# Sheet_5.net
KiCad netlist of a schematic drawn in Altium Designer
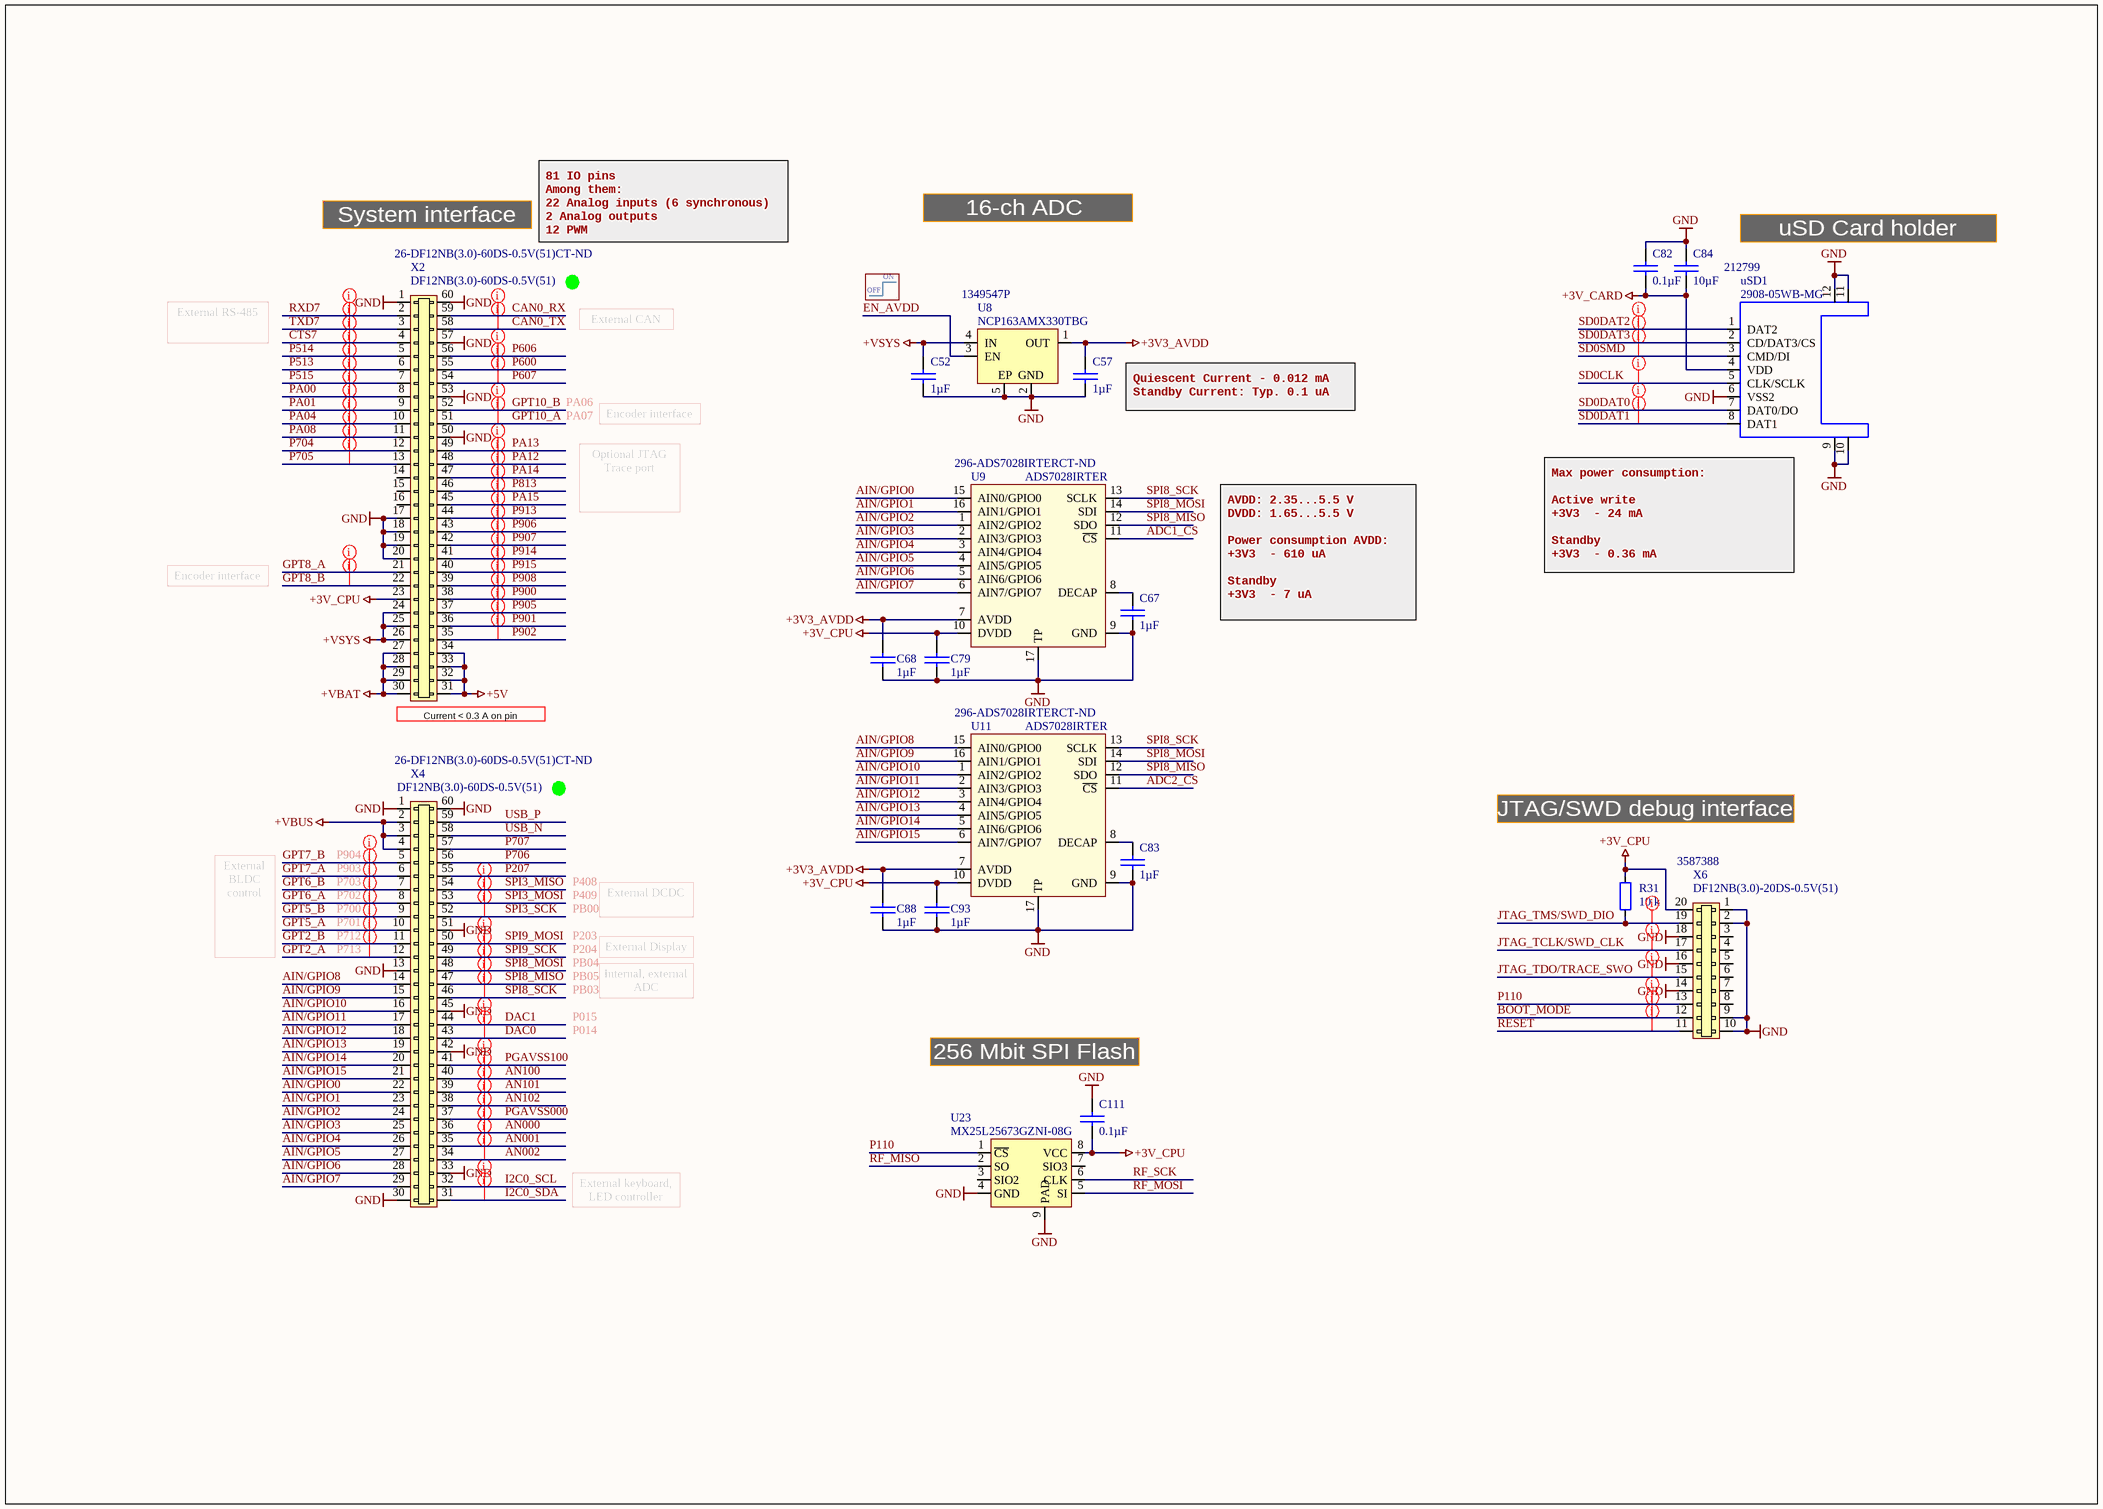
[diagram p0: Sheet_5.SchDoc]

(export (version "E")
  (design (tool "Eeschema 10.0.6"))
  (components
    (comp (ref "C52")
      (value "1µF")
      (footprint "0402 CAP")
      (description "1µF, ±20%, 25V, X5R, 0402 (1005 Metric), -55°C ~ 85°C, -, General Purpose")
      (fields (field (name "PART NUMBER") "TMK105BJ105MV-F") (field (name "MANUFACTURER") "Taiyo Yuden"))
      (libsource (lib "ea_PassivComps") (part "Capacitor"))
    )
    (comp (ref "C57")
      (value "1µF")
      (footprint "0402 CAP")
      (description "1µF, ±20%, 25V, X5R, 0402 (1005 Metric), -55°C ~ 85°C, -, General Purpose")
      (fields (field (name "PART NUMBER") "TMK105BJ105MV-F") (field (name "MANUFACTURER") "Taiyo Yuden"))
      (libsource (lib "ea_PassivComps") (part "Capacitor"))
    )
    (comp (ref "C67")
      (value "1µF")
      (footprint "0402 CAP")
      (description "1µF, ±20%, 25V, X5R, 0402 (1005 Metric), -55°C ~ 85°C, -, General Purpose")
      (fields (field (name "PART NUMBER") "TMK105BJ105MV-F") (field (name "MANUFACTURER") "Taiyo Yuden"))
      (libsource (lib "ea_PassivComps") (part "Capacitor"))
    )
    (comp (ref "C68")
      (value "1µF")
      (footprint "0402 CAP")
      (description "1µF, ±20%, 25V, X5R, 0402 (1005 Metric), -55°C ~ 85°C, -, General Purpose")
      (fields (field (name "PART NUMBER") "TMK105BJ105MV-F") (field (name "MANUFACTURER") "Taiyo Yuden"))
      (libsource (lib "ea_PassivComps") (part "Capacitor"))
    )
    (comp (ref "C79")
      (value "1µF")
      (footprint "0402 CAP")
      (description "1µF, ±20%, 25V, X5R, 0402 (1005 Metric), -55°C ~ 85°C, -, General Purpose")
      (fields (field (name "PART NUMBER") "TMK105BJ105MV-F") (field (name "MANUFACTURER") "Taiyo Yuden"))
      (libsource (lib "ea_PassivComps") (part "Capacitor"))
    )
    (comp (ref "C82")
      (value "0.1µF")
      (footprint "0402 CAP")
      (description "0.1µF, ±10%, 50V, X7R, 0402 (1005 Metric), -55°C ~ 125°C, -, General Purpose")
      (fields
        (field (name "PART NUMBER") "0402B104K500CT")
        (field (name "MANUFACTURER") "Walsin Technology Corporation")
      )
      (libsource (lib "ea_PassivComps") (part "Capacitor"))
    )
    (comp (ref "C83")
      (value "1µF")
      (footprint "0402 CAP")
      (description "1µF, ±20%, 25V, X5R, 0402 (1005 Metric), -55°C ~ 85°C, -, General Purpose")
      (fields (field (name "PART NUMBER") "TMK105BJ105MV-F") (field (name "MANUFACTURER") "Taiyo Yuden"))
      (libsource (lib "ea_PassivComps") (part "Capacitor"))
    )
    (comp (ref "C84")
      (value "10µF")
      (footprint "0603 CAP")
      (description "10µF, ±10%, 16V, X5R, 0603 (1608 Metric), -55°C ~ 85°C, -, Automotive")
      (fields
        (field (name "PART NUMBER") "GRT188R61C106KE13D")
        (field (name "MANUFACTURER") "Murata Electronics North America")
      )
      (libsource (lib "ea_PassivComps") (part "Capacitor"))
    )
    (comp (ref "C88")
      (value "1µF")
      (footprint "0402 CAP")
      (description "1µF, ±20%, 25V, X5R, 0402 (1005 Metric), -55°C ~ 85°C, -, General Purpose")
      (fields (field (name "PART NUMBER") "TMK105BJ105MV-F") (field (name "MANUFACTURER") "Taiyo Yuden"))
      (libsource (lib "ea_PassivComps") (part "Capacitor"))
    )
    (comp (ref "C93")
      (value "1µF")
      (footprint "0402 CAP")
      (description "1µF, ±20%, 25V, X5R, 0402 (1005 Metric), -55°C ~ 85°C, -, General Purpose")
      (fields (field (name "PART NUMBER") "TMK105BJ105MV-F") (field (name "MANUFACTURER") "Taiyo Yuden"))
      (libsource (lib "ea_PassivComps") (part "Capacitor"))
    )
    (comp (ref "C111")
      (value "0.1µF")
      (footprint "0402 CAP")
      (description "0.1µF, ±10%, 50V, X7R, 0402 (1005 Metric), -55°C ~ 125°C, -, General Purpose")
      (fields
        (field (name "PART NUMBER") "0402B104K500CT")
        (field (name "MANUFACTURER") "Walsin Technology Corporation")
      )
      (libsource (lib "ea_PassivComps") (part "Capacitor"))
    )
    (comp (ref "R31")
      (value "10 k")
      (footprint "0402")
      (fields
        (field (name "MANUFACTURER") "Stackpole Electronics Inc")
        (field (name "TOLERANCE") "±1%")
        (field (name "PARTNUM") "RMCF0402FT10K0CT-ND")
      )
      (libsource (lib "ea_PassivComps") (part "Resistor"))
    )
    (comp (ref "U8")
      (value "NCP163AMX330TBG")
      (footprint "4-XDFN")
      (description "LDO 3.3V, 250 mA, Vin < 5.5V, Iq < 20uA, -40..+125 C,  4-XDFN (1x1)")
      (fields
        (field (name "MANUFACTURER") "ON Semiconductor")
        (field (name "PARTNUM") "NCP163AMX330TBGOSCT-ND")
        (field (name "SUPPLIER PART NUMBER 1") "1349547P")
      )
      (libsource (lib "ea_IC_Linear_reg_LDO") (part "NCP163AMX330TBG"))
    )
    (comp (ref "U9")
      (value "ADS7028IRTER")
      (footprint "WQFN-16 3x3mm TI")
      (description "12 Bit Analog to Digital Converter 8 Input 1 SAR, 2.35V ~ 5.5V, 16-WQFN (3x3),  -40°C ~ 85°C")
      (fields
        (field (name "MANUFACTURER") "Texas Instruments")
        (field (name "PARTNUM") "296-ADS7028IRTERCT-ND")
        (field (name "SUPPLIER PART NUMBER 1") "296-ADS7028IRTERCT-ND")
      )
      (libsource (lib "ea_IC_ADC") (part "ADS7028IRTER"))
    )
    (comp (ref "U11")
      (value "ADS7028IRTER")
      (footprint "WQFN-16 3x3mm TI")
      (description "12 Bit Analog to Digital Converter 8 Input 1 SAR, 2.35V ~ 5.5V, 16-WQFN (3x3),  -40°C ~ 85°C")
      (fields
        (field (name "MANUFACTURER") "Texas Instruments")
        (field (name "PARTNUM") "296-ADS7028IRTERCT-ND")
        (field (name "SUPPLIER PART NUMBER 1") "296-ADS7028IRTERCT-ND")
      )
      (libsource (lib "ea_IC_ADC") (part "ADS7028IRTER"))
    )
    (comp (ref "U23")
      (value "MX25L25673GZNI-08G")
      (footprint "DFN8")
      (description "FLASH - NOR Memory IC 256Mbit SPI 120 MHz, 2.7V ~ 3.6V, 8-WSON (6x5), -40°C ~ 85°C (TA)")
      (fields
        (field (name "MANUFACTURER") "Kioxia America, Inc.")
        (field (name "PARTNUM") "TC58CVG1S3HRAIG-ND")
      )
      (libsource (lib "ea_IC_NOR_NAND_FLASH") (part "MX25L25673GZNI-08G"))
    )
    (comp (ref "uSD1")
      (value "2908-05WB-MG")
      (footprint "2908-05WB-MG")
      (description "microSD cadr holder")
      (fields (field (name "MANUFACTURER") "3M") (field (name "SUPPLIER PART NUMBER 1") "212799"))
      (libsource (lib "ea_CARD_holders") (part "2908-05WB-MG"))
    )
    (comp (ref "X2")
      (value "DF12NB(3.0)-60DS-0.5V(51)")
      (footprint "DF12NB(3.0)-60DS-0.5V(51)")
      (fields
        (field (name "MANUFACTURER") "Hirose Electric")
        (field (name "PARTNUM") "26-DF12NB(3.0)-60DS-0.5V(51)CT-ND")
        (field (name "SUPPLIER PART NUMBER 1") "26-DF12NB(3.0)-60DS-0.5V(51)CT-ND")
      )
      (libsource (lib "ea_Connectors_0.5_mm_pitch") (part "DF12NB(3.0)-60DS-0.5V(51)"))
    )
    (comp (ref "X4")
      (value "DF12NB(3.0)-60DS-0.5V(51)")
      (footprint "DF12NB(3.0)-60DS-0.5V(51)")
      (fields
        (field (name "MANUFACTURER") "Hirose Electric")
        (field (name "PARTNUM") "26-DF12NB(3.0)-60DS-0.5V(51)CT-ND")
        (field (name "SUPPLIER PART NUMBER 1") "26-DF12NB(3.0)-60DS-0.5V(51)CT-ND")
      )
      (libsource (lib "ea_Connectors_0.5_mm_pitch") (part "DF12NB(3.0)-60DS-0.5V(51)"))
    )
    (comp (ref "X6")
      (value "DF12NB(3.0)-20DS-0.5V(51)")
      (footprint "DF12NB(3.0)-20DS-0.5V(51)")
      (fields
        (field (name "MANUFACTURER") "Hirose Electric")
        (field (name "PARTNUM") "26-DF12NB(3.0)-20DS-0.5V(51)CT-ND - Cut Tape (CT)")
        (field (name "SUPPLIER PART NUMBER 1") "3587388")
      )
      (libsource (lib "ea_Connectors_0.5_mm_pitch") (part "DF12NB(3.0)-20DS-0.5V(51)"))
    )
  )
  (nets
    (net (code "1") (name "+3V3_AVDD") (class "Default")
      (node (ref "C57") (pin "1") (pinfunction "1_1") (pintype "passive"))
      (node (ref "C68") (pin "1") (pinfunction "1_1") (pintype "passive"))
      (node (ref "C88") (pin "1") (pinfunction "1_1") (pintype "passive"))
      (node (ref "U11") (pin "7") (pinfunction "AVDD_7") (pintype "passive"))
      (node (ref "U8") (pin "1") (pinfunction "OUT_1") (pintype "power_in"))
      (node (ref "U9") (pin "7") (pinfunction "AVDD_7") (pintype "passive"))
    )
    (net (code "2") (name "+3V_CARD") (class "Default")
      (node (ref "C82") (pin "2") (pinfunction "2_2") (pintype "passive"))
      (node (ref "C84") (pin "2") (pinfunction "2_2") (pintype "passive"))
      (node (ref "uSD1") (pin "4") (pinfunction "VDD_4") (pintype "passive"))
    )
    (net (code "3") (name "+3V_CPU") (class "Default")
      (node (ref "C111") (pin "2") (pinfunction "2_2") (pintype "passive"))
      (node (ref "C79") (pin "1") (pinfunction "1_1") (pintype "passive"))
      (node (ref "C93") (pin "1") (pinfunction "1_1") (pintype "passive"))
      (node (ref "R31") (pin "2") (pinfunction "2_2") (pintype "passive"))
      (node (ref "U11") (pin "10") (pinfunction "DVDD_10") (pintype "passive"))
      (node (ref "U23") (pin "8") (pinfunction "VCC_8") (pintype "passive"))
      (node (ref "U9") (pin "10") (pinfunction "DVDD_10") (pintype "passive"))
      (node (ref "X2") (pin "23") (pinfunction "23_23") (pintype "passive"))
      (node (ref "X6") (pin "20") (pinfunction "11_20") (pintype "passive"))
    )
    (net (code "4") (name "+5V") (class "Default")
      (node (ref "X2") (pin "31") (pinfunction "31_31") (pintype "passive"))
      (node (ref "X2") (pin "32") (pinfunction "32_32") (pintype "passive"))
      (node (ref "X2") (pin "33") (pinfunction "33_33") (pintype "passive"))
      (node (ref "X2") (pin "34") (pinfunction "34_34") (pintype "passive"))
    )
    (net (code "5") (name "+VBAT") (class "Default")
      (node (ref "X2") (pin "27") (pinfunction "27_27") (pintype "passive"))
      (node (ref "X2") (pin "28") (pinfunction "28_28") (pintype "passive"))
      (node (ref "X2") (pin "29") (pinfunction "29_29") (pintype "passive"))
      (node (ref "X2") (pin "30") (pinfunction "30_30") (pintype "passive"))
    )
    (net (code "6") (name "+VBUS") (class "Default")
      (node (ref "X4") (pin "2") (pinfunction "2_2") (pintype "passive"))
      (node (ref "X4") (pin "3") (pinfunction "3_3") (pintype "passive"))
      (node (ref "X4") (pin "4") (pinfunction "4_4") (pintype "passive"))
    )
    (net (code "7") (name "+VSYS") (class "Default")
      (node (ref "C52") (pin "1") (pinfunction "1_1") (pintype "passive"))
      (node (ref "U8") (pin "4") (pinfunction "IN_4") (pintype "power_in"))
      (node (ref "X2") (pin "24") (pinfunction "24_24") (pintype "passive"))
      (node (ref "X2") (pin "25") (pinfunction "25_25") (pintype "passive"))
      (node (ref "X2") (pin "26") (pinfunction "26_26") (pintype "passive"))
    )
    (net (code "8") (name "/ADC1_CS") (class "Default")
      (node (ref "U9") (pin "11") (pinfunction "~{CS}_11") (pintype "passive"))
    )
    (net (code "9") (name "/ADC2_CS") (class "Default")
      (node (ref "U11") (pin "11") (pinfunction "~{CS}_11") (pintype "passive"))
    )
    (net (code "10") (name "/AIN{slash}GPIO0") (class "Default")
      (node (ref "U9") (pin "15") (pinfunction "AIN0/GPIO0_15") (pintype "passive"))
      (node (ref "X4") (pin "22") (pinfunction "22_22") (pintype "passive"))
    )
    (net (code "11") (name "/AIN{slash}GPIO1") (class "Default")
      (node (ref "U9") (pin "16") (pinfunction "AIN1/GPIO1_16") (pintype "passive"))
      (node (ref "X4") (pin "23") (pinfunction "23_23") (pintype "passive"))
    )
    (net (code "12") (name "/AIN{slash}GPIO2") (class "Default")
      (node (ref "U9") (pin "1") (pinfunction "AIN2/GPIO2_1") (pintype "passive"))
      (node (ref "X4") (pin "24") (pinfunction "24_24") (pintype "passive"))
    )
    (net (code "13") (name "/AIN{slash}GPIO3") (class "Default")
      (node (ref "U9") (pin "2") (pinfunction "AIN3/GPIO3_2") (pintype "passive"))
      (node (ref "X4") (pin "25") (pinfunction "25_25") (pintype "passive"))
    )
    (net (code "14") (name "/AIN{slash}GPIO4") (class "Default")
      (node (ref "U9") (pin "3") (pinfunction "AIN4/GPIO4_3") (pintype "passive"))
      (node (ref "X4") (pin "26") (pinfunction "26_26") (pintype "passive"))
    )
    (net (code "15") (name "/AIN{slash}GPIO5") (class "Default")
      (node (ref "U9") (pin "4") (pinfunction "AIN5/GPIO5_4") (pintype "passive"))
      (node (ref "X4") (pin "27") (pinfunction "27_27") (pintype "passive"))
    )
    (net (code "16") (name "/AIN{slash}GPIO6") (class "Default")
      (node (ref "U9") (pin "5") (pinfunction "AIN6/GPIO6_5") (pintype "passive"))
      (node (ref "X4") (pin "28") (pinfunction "28_28") (pintype "passive"))
    )
    (net (code "17") (name "/AIN{slash}GPIO7") (class "Default")
      (node (ref "U9") (pin "6") (pinfunction "AIN7/GPIO7_6") (pintype "passive"))
      (node (ref "X4") (pin "29") (pinfunction "29_29") (pintype "passive"))
    )
    (net (code "18") (name "/AIN{slash}GPIO8") (class "Default")
      (node (ref "U11") (pin "15") (pinfunction "AIN0/GPIO0_15") (pintype "passive"))
      (node (ref "X4") (pin "14") (pinfunction "14_14") (pintype "passive"))
    )
    (net (code "19") (name "/AIN{slash}GPIO9") (class "Default")
      (node (ref "U11") (pin "16") (pinfunction "AIN1/GPIO1_16") (pintype "passive"))
      (node (ref "X4") (pin "15") (pinfunction "15_15") (pintype "passive"))
    )
    (net (code "20") (name "/AIN{slash}GPIO10") (class "Default")
      (node (ref "U11") (pin "1") (pinfunction "AIN2/GPIO2_1") (pintype "passive"))
      (node (ref "X4") (pin "16") (pinfunction "16_16") (pintype "passive"))
    )
    (net (code "21") (name "/AIN{slash}GPIO11") (class "Default")
      (node (ref "U11") (pin "2") (pinfunction "AIN3/GPIO3_2") (pintype "passive"))
      (node (ref "X4") (pin "17") (pinfunction "17_17") (pintype "passive"))
    )
    (net (code "22") (name "/AIN{slash}GPIO12") (class "Default")
      (node (ref "U11") (pin "3") (pinfunction "AIN4/GPIO4_3") (pintype "passive"))
      (node (ref "X4") (pin "18") (pinfunction "18_18") (pintype "passive"))
    )
    (net (code "23") (name "/AIN{slash}GPIO13") (class "Default")
      (node (ref "U11") (pin "4") (pinfunction "AIN5/GPIO5_4") (pintype "passive"))
      (node (ref "X4") (pin "19") (pinfunction "19_19") (pintype "passive"))
    )
    (net (code "24") (name "/AIN{slash}GPIO14") (class "Default")
      (node (ref "U11") (pin "5") (pinfunction "AIN6/GPIO6_5") (pintype "passive"))
      (node (ref "X4") (pin "20") (pinfunction "20_20") (pintype "passive"))
    )
    (net (code "25") (name "/AIN{slash}GPIO15") (class "Default")
      (node (ref "U11") (pin "6") (pinfunction "AIN7/GPIO7_6") (pintype "passive"))
      (node (ref "X4") (pin "21") (pinfunction "21_21") (pintype "passive"))
    )
    (net (code "26") (name "/AN000") (class "Default")
      (node (ref "X4") (pin "36") (pinfunction "36_36") (pintype "passive"))
    )
    (net (code "27") (name "/AN001") (class "Default")
      (node (ref "X4") (pin "35") (pinfunction "35_35") (pintype "passive"))
    )
    (net (code "28") (name "/AN002") (class "Default")
      (node (ref "X4") (pin "34") (pinfunction "34_34") (pintype "passive"))
    )
    (net (code "29") (name "/AN100") (class "Default")
      (node (ref "X4") (pin "40") (pinfunction "40_40") (pintype "passive"))
    )
    (net (code "30") (name "/AN101") (class "Default")
      (node (ref "X4") (pin "39") (pinfunction "39_39") (pintype "passive"))
    )
    (net (code "31") (name "/AN102") (class "Default")
      (node (ref "X4") (pin "38") (pinfunction "38_38") (pintype "passive"))
    )
    (net (code "32") (name "/BOOT_MODE") (class "Default")
      (node (ref "X6") (pin "12") (pinfunction "7_12") (pintype "passive"))
    )
    (net (code "33") (name "/CAN0_RX") (class "Default")
      (node (ref "X2") (pin "59") (pinfunction "59_59") (pintype "passive"))
    )
    (net (code "34") (name "/CAN0_TX") (class "Default")
      (node (ref "X2") (pin "58") (pinfunction "58_58") (pintype "passive"))
    )
    (net (code "35") (name "/CTS7") (class "Default")
      (node (ref "X2") (pin "4") (pinfunction "4_4") (pintype "passive"))
    )
    (net (code "36") (name "/DAC0") (class "Default")
      (node (ref "X4") (pin "43") (pinfunction "43_43") (pintype "passive"))
    )
    (net (code "37") (name "/DAC1") (class "Default")
      (node (ref "X4") (pin "44") (pinfunction "44_44") (pintype "passive"))
    )
    (net (code "38") (name "/EN_AVDD") (class "Default")
      (node (ref "U8") (pin "3") (pinfunction "EN_3") (pintype "power_in"))
    )
    (net (code "39") (name "/GPT2_A") (class "Default")
      (node (ref "X4") (pin "12") (pinfunction "12_12") (pintype "passive"))
    )
    (net (code "40") (name "/GPT2_B") (class "Default")
      (node (ref "X4") (pin "11") (pinfunction "11_11") (pintype "passive"))
    )
    (net (code "41") (name "/GPT5_A") (class "Default")
      (node (ref "X4") (pin "10") (pinfunction "10_10") (pintype "passive"))
    )
    (net (code "42") (name "/GPT5_B") (class "Default")
      (node (ref "X4") (pin "9") (pinfunction "9_9") (pintype "passive"))
    )
    (net (code "43") (name "/GPT6_A") (class "Default")
      (node (ref "X4") (pin "8") (pinfunction "8_8") (pintype "passive"))
    )
    (net (code "44") (name "/GPT6_B") (class "Default")
      (node (ref "X4") (pin "7") (pinfunction "7_7") (pintype "passive"))
    )
    (net (code "45") (name "/GPT7_A") (class "Default")
      (node (ref "X4") (pin "6") (pinfunction "6_6") (pintype "passive"))
    )
    (net (code "46") (name "/GPT7_B") (class "Default")
      (node (ref "X4") (pin "5") (pinfunction "5_5") (pintype "passive"))
    )
    (net (code "47") (name "/GPT8_A") (class "Default")
      (node (ref "X2") (pin "21") (pinfunction "21_21") (pintype "passive"))
    )
    (net (code "48") (name "/GPT8_B") (class "Default")
      (node (ref "X2") (pin "22") (pinfunction "22_22") (pintype "passive"))
    )
    (net (code "49") (name "/GPT10_A") (class "Default")
      (node (ref "X2") (pin "51") (pinfunction "51_51") (pintype "passive"))
    )
    (net (code "50") (name "/GPT10_B") (class "Default")
      (node (ref "X2") (pin "52") (pinfunction "52_52") (pintype "passive"))
    )
    (net (code "51") (name "/I2C0_SCL") (class "Default")
      (node (ref "X4") (pin "32") (pinfunction "32_32") (pintype "passive"))
    )
    (net (code "52") (name "/I2C0_SDA") (class "Default")
      (node (ref "X4") (pin "31") (pinfunction "31_31") (pintype "passive"))
    )
    (net (code "53") (name "/JTAG_TCLK{slash}SWD_CLK") (class "Default")
      (node (ref "X6") (pin "17") (pinfunction "9_17") (pintype "passive"))
    )
    (net (code "54") (name "/JTAG_TDO{slash}TRACE_SWO") (class "Default")
      (node (ref "X6") (pin "15") (pinfunction "8_15") (pintype "passive"))
    )
    (net (code "55") (name "/JTAG_TMS{slash}SWD_DIO") (class "Default")
      (node (ref "R31") (pin "1") (pinfunction "1_1") (pintype "passive"))
      (node (ref "X6") (pin "19") (pinfunction "10_19") (pintype "passive"))
    )
    (net (code "56") (name "/P110") (class "Default")
      (node (ref "U23") (pin "1") (pinfunction "~{CS}_1") (pintype "passive"))
      (node (ref "X6") (pin "13") (pinfunction "7_13") (pintype "passive"))
    )
    (net (code "57") (name "/P207") (class "Default")
      (node (ref "X4") (pin "55") (pinfunction "55_55") (pintype "passive"))
    )
    (net (code "58") (name "/P513") (class "Default")
      (node (ref "X2") (pin "6") (pinfunction "6_6") (pintype "passive"))
    )
    (net (code "59") (name "/P514") (class "Default")
      (node (ref "X2") (pin "5") (pinfunction "5_5") (pintype "passive"))
    )
    (net (code "60") (name "/P515") (class "Default")
      (node (ref "X2") (pin "7") (pinfunction "7_7") (pintype "passive"))
    )
    (net (code "61") (name "/P600") (class "Default")
      (node (ref "X2") (pin "55") (pinfunction "55_55") (pintype "passive"))
    )
    (net (code "62") (name "/P606") (class "Default")
      (node (ref "X2") (pin "56") (pinfunction "56_56") (pintype "passive"))
    )
    (net (code "63") (name "/P607") (class "Default")
      (node (ref "X2") (pin "54") (pinfunction "54_54") (pintype "passive"))
    )
    (net (code "64") (name "/P704") (class "Default")
      (node (ref "X2") (pin "12") (pinfunction "12_12") (pintype "passive"))
    )
    (net (code "65") (name "/P705") (class "Default")
      (node (ref "X2") (pin "13") (pinfunction "13_13") (pintype "passive"))
    )
    (net (code "66") (name "/P706") (class "Default")
      (node (ref "X4") (pin "56") (pinfunction "56_56") (pintype "passive"))
    )
    (net (code "67") (name "/P707") (class "Default")
      (node (ref "X4") (pin "57") (pinfunction "57_57") (pintype "passive"))
    )
    (net (code "68") (name "/P813") (class "Default")
      (node (ref "X2") (pin "46") (pinfunction "46_46") (pintype "passive"))
    )
    (net (code "69") (name "/P900") (class "Default")
      (node (ref "X2") (pin "38") (pinfunction "38_38") (pintype "passive"))
    )
    (net (code "70") (name "/P901") (class "Default")
      (node (ref "X2") (pin "36") (pinfunction "36_36") (pintype "passive"))
    )
    (net (code "71") (name "/P902") (class "Default")
      (node (ref "X2") (pin "35") (pinfunction "35_35") (pintype "passive"))
    )
    (net (code "72") (name "/P905") (class "Default")
      (node (ref "X2") (pin "37") (pinfunction "37_37") (pintype "passive"))
    )
    (net (code "73") (name "/P906") (class "Default")
      (node (ref "X2") (pin "43") (pinfunction "43_43") (pintype "passive"))
    )
    (net (code "74") (name "/P907") (class "Default")
      (node (ref "X2") (pin "42") (pinfunction "42_42") (pintype "passive"))
    )
    (net (code "75") (name "/P908") (class "Default")
      (node (ref "X2") (pin "39") (pinfunction "39_39") (pintype "passive"))
    )
    (net (code "76") (name "/P913") (class "Default")
      (node (ref "X2") (pin "44") (pinfunction "44_44") (pintype "passive"))
    )
    (net (code "77") (name "/P914") (class "Default")
      (node (ref "X2") (pin "41") (pinfunction "41_41") (pintype "passive"))
    )
    (net (code "78") (name "/P915") (class "Default")
      (node (ref "X2") (pin "40") (pinfunction "40_40") (pintype "passive"))
    )
    (net (code "79") (name "/PA00") (class "Default")
      (node (ref "X2") (pin "8") (pinfunction "8_8") (pintype "passive"))
    )
    (net (code "80") (name "/PA01") (class "Default")
      (node (ref "X2") (pin "9") (pinfunction "9_9") (pintype "passive"))
    )
    (net (code "81") (name "/PA04") (class "Default")
      (node (ref "X2") (pin "10") (pinfunction "10_10") (pintype "passive"))
    )
    (net (code "82") (name "/PA08") (class "Default")
      (node (ref "X2") (pin "11") (pinfunction "11_11") (pintype "passive"))
    )
    (net (code "83") (name "/PA12") (class "Default")
      (node (ref "X2") (pin "48") (pinfunction "48_48") (pintype "passive"))
    )
    (net (code "84") (name "/PA13") (class "Default")
      (node (ref "X2") (pin "49") (pinfunction "49_49") (pintype "passive"))
    )
    (net (code "85") (name "/PA14") (class "Default")
      (node (ref "X2") (pin "47") (pinfunction "47_47") (pintype "passive"))
    )
    (net (code "86") (name "/PA15") (class "Default")
      (node (ref "X2") (pin "45") (pinfunction "45_45") (pintype "passive"))
    )
    (net (code "87") (name "/PGAVSS000") (class "Default")
      (node (ref "X4") (pin "37") (pinfunction "37_37") (pintype "passive"))
    )
    (net (code "88") (name "/PGAVSS100") (class "Default")
      (node (ref "X4") (pin "41") (pinfunction "41_41") (pintype "passive"))
    )
    (net (code "89") (name "/RESET") (class "Default")
      (node (ref "X6") (pin "11") (pinfunction "6_11") (pintype "passive"))
    )
    (net (code "90") (name "/RF_MISO") (class "Default")
      (node (ref "U23") (pin "2") (pinfunction "SO_2") (pintype "passive"))
    )
    (net (code "91") (name "/RF_MOSI") (class "Default")
      (node (ref "U23") (pin "5") (pinfunction "SI_5") (pintype "passive"))
    )
    (net (code "92") (name "/RF_SCK") (class "Default")
      (node (ref "U23") (pin "6") (pinfunction "CLK_6") (pintype "passive"))
    )
    (net (code "93") (name "/RXD7") (class "Default")
      (node (ref "X2") (pin "2") (pinfunction "2_2") (pintype "passive"))
    )
    (net (code "94") (name "/SD0CLK") (class "Default")
      (node (ref "uSD1") (pin "5") (pinfunction "CLK/SCLK_5") (pintype "passive"))
    )
    (net (code "95") (name "/SD0DAT0") (class "Default")
      (node (ref "uSD1") (pin "7") (pinfunction "DAT0/DO_7") (pintype "passive"))
    )
    (net (code "96") (name "/SD0DAT1") (class "Default")
      (node (ref "uSD1") (pin "8") (pinfunction "DAT1_8") (pintype "passive"))
    )
    (net (code "97") (name "/SD0DAT2") (class "Default")
      (node (ref "uSD1") (pin "1") (pinfunction "DAT2_1") (pintype "passive"))
    )
    (net (code "98") (name "/SD0DAT3") (class "Default")
      (node (ref "uSD1") (pin "2") (pinfunction "CD/DAT3/CS_2") (pintype "passive"))
    )
    (net (code "99") (name "/SD0SMD") (class "Default")
      (node (ref "uSD1") (pin "3") (pinfunction "CMD/DI_3") (pintype "passive"))
    )
    (net (code "100") (name "/SPI3_MISO") (class "Default")
      (node (ref "X4") (pin "54") (pinfunction "54_54") (pintype "passive"))
    )
    (net (code "101") (name "/SPI3_MOSI") (class "Default")
      (node (ref "X4") (pin "53") (pinfunction "53_53") (pintype "passive"))
    )
    (net (code "102") (name "/SPI3_SCK") (class "Default")
      (node (ref "X4") (pin "52") (pinfunction "52_52") (pintype "passive"))
    )
    (net (code "103") (name "/SPI8_MISO") (class "Default")
      (node (ref "U11") (pin "12") (pinfunction "SDO_12") (pintype "passive"))
      (node (ref "U9") (pin "12") (pinfunction "SDO_12") (pintype "passive"))
      (node (ref "X4") (pin "47") (pinfunction "47_47") (pintype "passive"))
    )
    (net (code "104") (name "/SPI8_MOSI") (class "Default")
      (node (ref "U11") (pin "14") (pinfunction "SDI_14") (pintype "passive"))
      (node (ref "U9") (pin "14") (pinfunction "SDI_14") (pintype "passive"))
      (node (ref "X4") (pin "48") (pinfunction "48_48") (pintype "passive"))
    )
    (net (code "105") (name "/SPI8_SCK") (class "Default")
      (node (ref "U11") (pin "13") (pinfunction "SCLK_13") (pintype "passive"))
      (node (ref "U9") (pin "13") (pinfunction "SCLK_13") (pintype "passive"))
      (node (ref "X4") (pin "46") (pinfunction "46_46") (pintype "passive"))
    )
    (net (code "106") (name "/SPI9_MOSI") (class "Default")
      (node (ref "X4") (pin "50") (pinfunction "50_50") (pintype "passive"))
    )
    (net (code "107") (name "/SPI9_SCK") (class "Default")
      (node (ref "X4") (pin "49") (pinfunction "49_49") (pintype "passive"))
    )
    (net (code "108") (name "/TXD7") (class "Default")
      (node (ref "X2") (pin "3") (pinfunction "3_3") (pintype "passive"))
    )
    (net (code "109") (name "/USB_N") (class "Default")
      (node (ref "X4") (pin "58") (pinfunction "58_58") (pintype "passive"))
    )
    (net (code "110") (name "/USB_P") (class "Default")
      (node (ref "X4") (pin "59") (pinfunction "59_59") (pintype "passive"))
    )
    (net (code "111") (name "GND") (class "Default")
      (node (ref "C111") (pin "1") (pinfunction "1_1") (pintype "passive"))
      (node (ref "C52") (pin "2") (pinfunction "2_2") (pintype "passive"))
      (node (ref "C57") (pin "2") (pinfunction "2_2") (pintype "passive"))
      (node (ref "C67") (pin "2") (pinfunction "2_2") (pintype "passive"))
      (node (ref "C68") (pin "2") (pinfunction "2_2") (pintype "passive"))
      (node (ref "C79") (pin "2") (pinfunction "2_2") (pintype "passive"))
      (node (ref "C82") (pin "1") (pinfunction "1_1") (pintype "passive"))
      (node (ref "C83") (pin "2") (pinfunction "2_2") (pintype "passive"))
      (node (ref "C84") (pin "1") (pinfunction "1_1") (pintype "passive"))
      (node (ref "C88") (pin "2") (pinfunction "2_2") (pintype "passive"))
      (node (ref "C93") (pin "2") (pinfunction "2_2") (pintype "passive"))
      (node (ref "U11") (pin "17") (pinfunction "TP_17") (pintype "passive"))
      (node (ref "U11") (pin "9") (pinfunction "GND_9") (pintype "passive"))
      (node (ref "U23") (pin "4") (pinfunction "GND_4") (pintype "passive"))
      (node (ref "U23") (pin "9") (pinfunction "PAD_9") (pintype "passive"))
      (node (ref "U8") (pin "2") (pinfunction "GND_2") (pintype "power_in"))
      (node (ref "U8") (pin "5") (pinfunction "EP_5") (pintype "power_in"))
      (node (ref "U9") (pin "17") (pinfunction "TP_17") (pintype "passive"))
      (node (ref "U9") (pin "9") (pinfunction "GND_9") (pintype "passive"))
      (node (ref "X2") (pin "1") (pinfunction "1_1") (pintype "passive"))
      (node (ref "X2") (pin "17") (pinfunction "17_17") (pintype "passive"))
      (node (ref "X2") (pin "18") (pinfunction "18_18") (pintype "passive"))
      (node (ref "X2") (pin "19") (pinfunction "19_19") (pintype "passive"))
      (node (ref "X2") (pin "20") (pinfunction "20_20") (pintype "passive"))
      (node (ref "X2") (pin "50") (pinfunction "50_50") (pintype "passive"))
      (node (ref "X2") (pin "53") (pinfunction "53_53") (pintype "passive"))
      (node (ref "X2") (pin "57") (pinfunction "57_57") (pintype "passive"))
      (node (ref "X2") (pin "60") (pinfunction "60_60") (pintype "passive"))
      (node (ref "X4") (pin "1") (pinfunction "1_1") (pintype "passive"))
      (node (ref "X4") (pin "13") (pinfunction "13_13") (pintype "passive"))
      (node (ref "X4") (pin "30") (pinfunction "30_30") (pintype "passive"))
      (node (ref "X4") (pin "33") (pinfunction "33_33") (pintype "passive"))
      (node (ref "X4") (pin "42") (pinfunction "42_42") (pintype "passive"))
      (node (ref "X4") (pin "45") (pinfunction "45_45") (pintype "passive"))
      (node (ref "X4") (pin "51") (pinfunction "51_51") (pintype "passive"))
      (node (ref "X4") (pin "60") (pinfunction "60_60") (pintype "passive"))
      (node (ref "X6") (pin "1") (pinfunction "1_1") (pintype "passive"))
      (node (ref "X6") (pin "10") (pinfunction "6_10") (pintype "passive"))
      (node (ref "X6") (pin "14") (pinfunction "8_14") (pintype "passive"))
      (node (ref "X6") (pin "16") (pinfunction "9_16") (pintype "passive"))
      (node (ref "X6") (pin "18") (pinfunction "10_18") (pintype "passive"))
      (node (ref "X6") (pin "2") (pinfunction "2_2") (pintype "passive"))
      (node (ref "X6") (pin "9") (pinfunction "5_9") (pintype "passive"))
      (node (ref "uSD1") (pin "10") (pinfunction "WP_10") (pintype "passive"))
      (node (ref "uSD1") (pin "11") (pinfunction "GND_11") (pintype "passive"))
      (node (ref "uSD1") (pin "12") (pinfunction "GND_12") (pintype "passive"))
      (node (ref "uSD1") (pin "6") (pinfunction "VSS2_6") (pintype "passive"))
      (node (ref "uSD1") (pin "9") (pintype "passive"))
    )
    (net (code "112") (name "Net-(U9-DECAP)") (class "Default")
      (node (ref "C67") (pin "1") (pinfunction "1_1") (pintype "passive"))
      (node (ref "U9") (pin "8") (pinfunction "DECAP_8") (pintype "passive"))
    )
    (net (code "113") (name "Net-(U11-DECAP)") (class "Default")
      (node (ref "C83") (pin "1") (pinfunction "1_1") (pintype "passive"))
      (node (ref "U11") (pin "8") (pinfunction "DECAP_8") (pintype "passive"))
    )
    (net (code "114") (name "unconnected-(U23-SIO2-Pad3)") (class "Default")
      (node (ref "U23") (pin "3") (pinfunction "SIO2_3") (pintype "passive"))
    )
    (net (code "115") (name "unconnected-(U23-SIO3-Pad7)") (class "Default")
      (node (ref "U23") (pin "7") (pinfunction "SIO3_7") (pintype "passive"))
    )
    (net (code "116") (name "unconnected-(X2-Pad14)") (class "Default")
      (node (ref "X2") (pin "14") (pinfunction "14_14") (pintype "passive"))
    )
    (net (code "117") (name "unconnected-(X2-Pad15)") (class "Default")
      (node (ref "X2") (pin "15") (pinfunction "15_15") (pintype "passive"))
    )
    (net (code "118") (name "unconnected-(X2-Pad16)") (class "Default")
      (node (ref "X2") (pin "16") (pinfunction "16_16") (pintype "passive"))
    )
    (net (code "119") (name "unconnected-(X6-2-Pad3)") (class "Default")
      (node (ref "X6") (pin "3") (pinfunction "2_3") (pintype "passive"))
    )
    (net (code "120") (name "unconnected-(X6-3-Pad4)") (class "Default")
      (node (ref "X6") (pin "4") (pinfunction "3_4") (pintype "passive"))
    )
    (net (code "121") (name "unconnected-(X6-3-Pad5)") (class "Default")
      (node (ref "X6") (pin "5") (pinfunction "3_5") (pintype "passive"))
    )
    (net (code "122") (name "unconnected-(X6-4-Pad6)") (class "Default")
      (node (ref "X6") (pin "6") (pinfunction "4_6") (pintype "passive"))
    )
    (net (code "123") (name "unconnected-(X6-4-Pad7)") (class "Default")
      (node (ref "X6") (pin "7") (pinfunction "4_7") (pintype "passive"))
    )
    (net (code "124") (name "unconnected-(X6-5-Pad8)") (class "Default")
      (node (ref "X6") (pin "8") (pinfunction "5_8") (pintype "passive"))
    )
  )
)
